# A2.net
KiCad netlist of a schematic drawn in Altium Designer
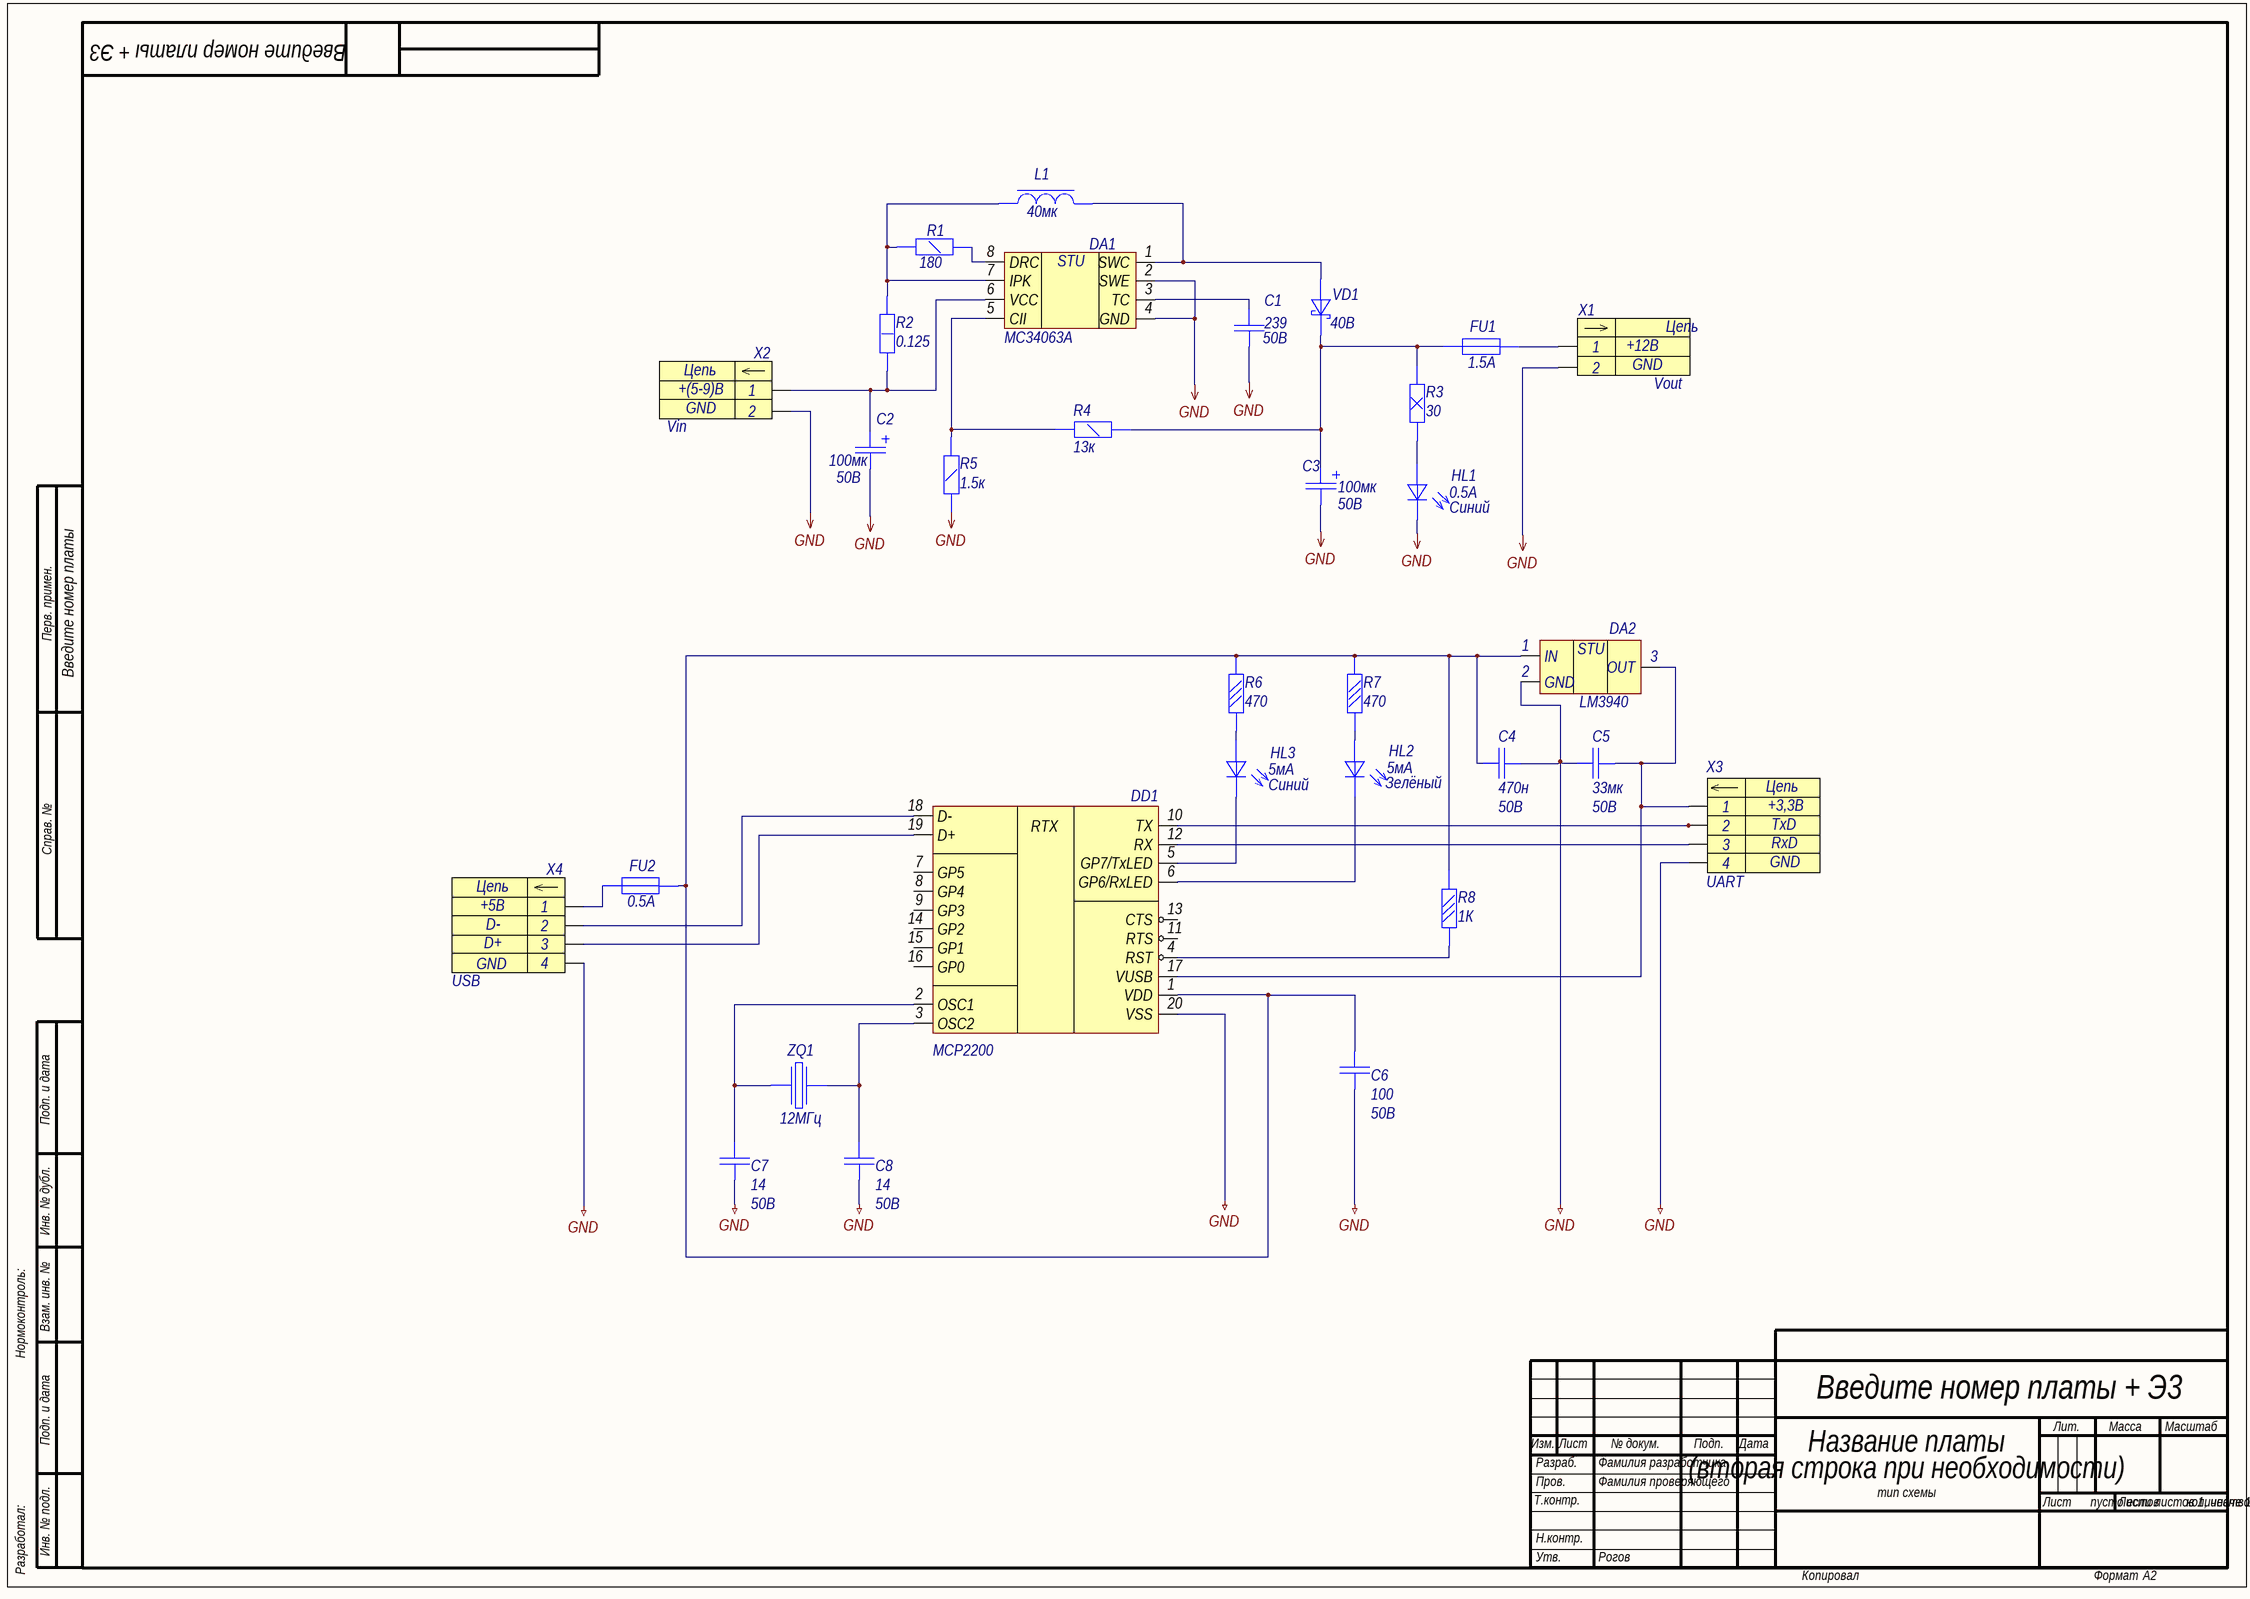
[diagram p0: A2.SchDoc]

(export (version "E")
  (design (tool "Eeschema 10.0.6"))
  (components
    (comp (ref "C1")
      (value "Capacitor")
      (footprint "R0805")
      (fields
        (field (name "ЁМКОСТЬ") "239")
        (field (name "НАПРЯЖЕНИЕ") "50В")
        (field (name "PUBLISHER") "Andrew Danich")
      )
      (libsource (lib "Capacitor GOST") (part "Capacitor"))
    )
    (comp (ref "C2")
      (value "Capacitor-E")
      (footprint "C1206")
      (fields
        (field (name "ЁМКОСТЬ") "100мк")
        (field (name "НАПРЯЖЕНИЕ") "50В")
        (field (name "PUBLISHER") "Олег Литвинов")
      )
      (libsource (lib "Capacitor GOST") (part "Capacitor-E"))
    )
    (comp (ref "C3")
      (value "Capacitor-E")
      (footprint "C1206")
      (fields
        (field (name "ЁМКОСТЬ") "100мк")
        (field (name "НАПРЯЖЕНИЕ") "50В")
        (field (name "PUBLISHER") "Олег Литвинов")
      )
      (libsource (lib "Capacitor GOST") (part "Capacitor-E"))
    )
    (comp (ref "C4")
      (value "470н")
      (footprint "C0805")
      (fields (field (name "VOLTAGE") "50В") (field (name "Comment") "Capacitor"))
      (libsource (lib "Capacitor_GOST") (part "Capacitor"))
    )
    (comp (ref "C5")
      (value "33мк")
      (footprint "C0805")
      (fields (field (name "VOLTAGE") "50В") (field (name "Comment") "Capacitor"))
      (libsource (lib "Capacitor_GOST") (part "Capacitor"))
    )
    (comp (ref "C6")
      (value "100")
      (footprint "C0805")
      (fields (field (name "VOLTAGE") "50В") (field (name "Comment") "Capacitor"))
      (libsource (lib "Capacitor_GOST") (part "Capacitor"))
    )
    (comp (ref "C7")
      (value "14")
      (footprint "C0805")
      (fields (field (name "VOLTAGE") "50В") (field (name "Comment") "Capacitor"))
      (libsource (lib "Capacitor_GOST") (part "Capacitor"))
    )
    (comp (ref "C8")
      (value "14")
      (footprint "C0805")
      (fields (field (name "VOLTAGE") "50В") (field (name "Comment") "Capacitor"))
      (libsource (lib "Capacitor_GOST") (part "Capacitor"))
    )
    (comp (ref "DA1")
      (value "MC34063A")
      (footprint "PCBComponent_1")
      (libsource (lib "MCP2200_UART_USB") (part "MC34063A"))
    )
    (comp (ref "DA2")
      (value "LM3940")
      (footprint "SOT95P255X145-3N")
      (fields (field (name "ITEM ID") "LM3940"))
      (libsource (lib "MCP2200_UART_USB") (part "LM3940"))
    )
    (comp (ref "DD1")
      (value "MCP2200")
      (footprint "SOIC127P1030X265-20N")
      (fields (field (name "WTF") "RTX") (field (name "CREATE") "Litvinov"))
      (libsource (lib "Schlib1") (part "MCP2200"))
    )
    (comp (ref "FU1")
      (value "1.5A")
      (footprint "F1812")
      (fields (field (name "Comment") "Fuse"))
      (libsource (lib "") (part "Fuse_1"))
    )
    (comp (ref "FU2")
      (value "0.5A")
      (footprint "F1812")
      (fields (field (name "Comment") "Fuse"))
      (libsource (lib "Fuse_GOST") (part "Fuse"))
    )
    (comp (ref "HL1")
      (value "LED_3V")
      (footprint "LD0805")
      (fields
        (field (name "ПРЯМОЙ ТОК") "0.5А")
        (field (name "ЦВЕТ") "Синий")
        (field (name "PUBLISHER") "Andrew Danich")
      )
      (libsource (lib "") (part "Led-1_1"))
    )
    (comp (ref "HL2")
      (value "LED_3V")
      (footprint "LD0805")
      (fields
        (field (name "ПРЯМОЙ ТОК") "5мА")
        (field (name "ЦВЕТ") "Зелёный")
        (field (name "PUBLISHER") "Andrew Danich")
      )
      (libsource (lib "Led GOST") (part "Led-1"))
    )
    (comp (ref "HL3")
      (value "LED_3V")
      (footprint "LD0805")
      (fields
        (field (name "ПРЯМОЙ ТОК") "5мА")
        (field (name "ЦВЕТ") "Синий")
        (field (name "PUBLISHER") "Andrew Danich")
      )
      (libsource (lib "Led GOST") (part "Led-1"))
    )
    (comp (ref "L1")
      (value "40мк")
      (footprint "МДГ-2")
      (fields
        (field (name "PART NUMBER") "КИВ18-100")
        (field (name "TOLERANCE") "±10%")
        (field (name "MANUFACTURER") "ОАО \"МСТАТОР\"")
        (field (name "PUBLISHER") "Andrew Danich")
      )
      (libsource (lib "Lib_GOST") (part "Coil"))
    )
    (comp (ref "R1")
      (value "Resistor_0,25W")
      (footprint "R0805")
      (fields (field (name "СОПРОТИВЛЕНИЕ") "180"))
      (libsource (lib "Resistor_GOST") (part "Resistor_0,25W"))
    )
    (comp (ref "R2")
      (value "0.125")
      (footprint "R0805")
      (fields (field (name "Comment") "Resistor_1,0W"))
      (libsource (lib "Resistor_GOST") (part "Resistor_1,0W"))
    )
    (comp (ref "R3")
      (value "Resistor_10,0W")
      (footprint "R0805")
      (fields (field (name "СОПРОТИВЛЕНИЕ") "30"))
      (libsource (lib "Resistor_GOST") (part "Resistor_10,0W"))
    )
    (comp (ref "R4")
      (value "13к")
      (fields (field (name "Comment") "Resistor_0,25W"))
      (libsource (lib "Resistor_GOST") (part "Resistor_0,25W"))
    )
    (comp (ref "R5")
      (value "1.5к")
      (footprint "R0805")
      (fields (field (name "Comment") "Resistor_0,25W"))
      (libsource (lib "Resistor_GOST") (part "Resistor_0,25W"))
    )
    (comp (ref "R6")
      (value "Resistor_0,05W")
      (footprint "R0805")
      (fields (field (name "СОПРОТИВЛЕНИЕ") "470"))
      (libsource (lib "") (part "Resistor_0,05W_2"))
    )
    (comp (ref "R7")
      (value "Resistor_0,05W")
      (footprint "R0805")
      (fields (field (name "СОПРОТИВЛЕНИЕ") "470"))
      (libsource (lib "Resistor_GOST") (part "Resistor_0,05W"))
    )
    (comp (ref "R8")
      (value "1К")
      (footprint "R0805")
      (fields (field (name "Comment") "Resistor_0,05W"))
      (libsource (lib "") (part "Resistor_0,05W_1"))
    )
    (comp (ref "VD1")
      (value "Schottky")
      (footprint "DO-214AC")
      (description "BYV10-40")
      (fields (field (name "МАКСИМАЛЬНОЕ ОБРАТНОЕ НАПРЯЖЕНИЕ") "40В"))
      (libsource (lib "Diode_GOST") (part "Schottky"))
    )
    (comp (ref "X1")
      (value "Vout")
      (footprint "CWF-2")
      (fields (field (name "U") "+12В") (field (name "GND") "GND") (field (name "CREATE") "DeathSpeaker"))
      (libsource (lib "MCP2200_UART_USB") (part "Vout"))
    )
    (comp (ref "X2")
      (value "Vin")
      (footprint "WF-2")
      (fields (field (name "U") "+(5-9)В") (field (name "GND") "GND") (field (name "CREATE") "DeathSpeaker"))
      (libsource (lib "MCP2200_UART_USB") (part "Vin"))
    )
    (comp (ref "X3")
      (value "UART")
      (footprint "UART")
      (fields
        (field (name "GND") "GND")
        (field (name "IN") "TxD")
        (field (name "OUT") "RxD")
        (field (name "U") "+3,3В")
        (field (name "CREATE") "Litvinov")
      )
      (libsource (lib "Schlib1") (part "UART"))
    )
    (comp (ref "X4")
      (value "USB")
      (footprint "USB")
      (fields
        (field (name "U") "+5В")
        (field (name "OUT") "D-")
        (field (name "IN") "D+")
        (field (name "GND") "GND")
        (field (name "CREATE") "Litvinov")
      )
      (libsource (lib "Schlib1") (part "USB"))
    )
    (comp (ref "ZQ1")
      (value "Crystal")
      (footprint "HC-49S")
      (fields (field (name "ЧАСТОТА") "12МГц") (field (name "PUBLISHER") "Andrew Danich"))
      (libsource (lib "Crystal GOST") (part "Crystal"))
    )
  )
  (nets
    (net (code "1") (name "GND") (class "Default")
      (node (ref "C1") (pin "1") (pinfunction "1_1") (pintype "passive"))
      (node (ref "C2") (pin "2") (pinfunction "2_2") (pintype "passive"))
      (node (ref "C3") (pin "2") (pinfunction "2_2") (pintype "passive"))
      (node (ref "C4") (pin "1") (pinfunction "1_1") (pintype "passive"))
      (node (ref "C5") (pin "2") (pinfunction "2_2") (pintype "passive"))
      (node (ref "C6") (pin "2") (pinfunction "2_2") (pintype "passive"))
      (node (ref "C7") (pin "1") (pinfunction "1_1") (pintype "passive"))
      (node (ref "C8") (pin "1") (pinfunction "1_1") (pintype "passive"))
      (node (ref "DA1") (pin "2") (pinfunction "SWE_2") (pintype "passive"))
      (node (ref "DA1") (pin "4") (pinfunction "GND_4") (pintype "passive"))
      (node (ref "DA2") (pin "2") (pinfunction "GND_2") (pintype "passive"))
      (node (ref "DD1") (pin "20") (pinfunction "VSS_20") (pintype "passive"))
      (node (ref "HL1") (pin "2") (pinfunction "К_2") (pintype "passive"))
      (node (ref "R5") (pin "1") (pinfunction "1_1") (pintype "passive"))
      (node (ref "X1") (pin "2") (pinfunction "2_2") (pintype "passive"))
      (node (ref "X2") (pin "2") (pinfunction "2_2") (pintype "passive"))
      (node (ref "X3") (pin "4") (pinfunction "4_4") (pintype "passive"))
      (node (ref "X4") (pin "4") (pinfunction "4_4") (pintype "passive"))
    )
    (net (code "2") (name "Net-(DA1-CII)") (class "Default")
      (node (ref "DA1") (pin "5") (pinfunction "CII_5") (pintype "passive"))
      (node (ref "R4") (pin "1") (pinfunction "1_1") (pintype "passive"))
      (node (ref "R5") (pin "2") (pinfunction "2_2") (pintype "passive"))
    )
    (net (code "3") (name "Net-(DA1-DRC)") (class "Default")
      (node (ref "DA1") (pin "8") (pinfunction "DRC_8") (pintype "passive"))
      (node (ref "R1") (pin "2") (pinfunction "2_2") (pintype "passive"))
    )
    (net (code "4") (name "Net-(DA1-IPK)") (class "Default")
      (node (ref "DA1") (pin "7") (pinfunction "IPK_7") (pintype "passive"))
      (node (ref "L1") (pin "1") (pinfunction "1_1") (pintype "passive"))
      (node (ref "R1") (pin "1") (pinfunction "1_1") (pintype "passive"))
      (node (ref "R2") (pin "2") (pinfunction "2_2") (pintype "passive"))
    )
    (net (code "5") (name "Net-(DA1-SWC)") (class "Default")
      (node (ref "DA1") (pin "1") (pinfunction "SWC_1") (pintype "passive"))
      (node (ref "L1") (pin "2") (pinfunction "2_2") (pintype "passive"))
      (node (ref "VD1") (pin "1") (pinfunction "А_1") (pintype "passive"))
    )
    (net (code "6") (name "Net-(DA1-TC)") (class "Default")
      (node (ref "C1") (pin "2") (pinfunction "2_2") (pintype "passive"))
      (node (ref "DA1") (pin "3") (pinfunction "TC_3") (pintype "passive"))
    )
    (net (code "7") (name "Net-(DA1-VCC)") (class "Default")
      (node (ref "C2") (pin "1") (pinfunction "1_1") (pintype "passive"))
      (node (ref "DA1") (pin "6") (pinfunction "VCC_6") (pintype "passive"))
      (node (ref "R2") (pin "1") (pinfunction "1_1") (pintype "passive"))
      (node (ref "X2") (pin "1") (pinfunction "1_1") (pintype "passive"))
    )
    (net (code "8") (name "Net-(DA2-IN)") (class "Default")
      (node (ref "C4") (pin "2") (pinfunction "2_2") (pintype "passive"))
      (node (ref "C6") (pin "1") (pinfunction "1_1") (pintype "passive"))
      (node (ref "DA2") (pin "1") (pinfunction "IN_1") (pintype "passive"))
      (node (ref "DD1") (pin "1") (pinfunction "VDD_1") (pintype "passive"))
      (node (ref "FU2") (pin "1") (pinfunction "1_1") (pintype "passive"))
      (node (ref "R6") (pin "2") (pinfunction "2_2") (pintype "passive"))
      (node (ref "R7") (pin "2") (pinfunction "2_2") (pintype "passive"))
      (node (ref "R8") (pin "2") (pinfunction "2_2") (pintype "passive"))
    )
    (net (code "9") (name "Net-(DA2-OUT)") (class "Default")
      (node (ref "C5") (pin "1") (pinfunction "1_1") (pintype "passive"))
      (node (ref "DA2") (pin "3") (pinfunction "OUT_3") (pintype "passive"))
      (node (ref "DD1") (pin "17") (pinfunction "VUSB_17") (pintype "passive"))
      (node (ref "X3") (pin "1") (pinfunction "1_1") (pintype "passive"))
    )
    (net (code "10") (name "Net-(DD1-D+)") (class "Default")
      (node (ref "DD1") (pin "19") (pinfunction "D+_19") (pintype "passive"))
      (node (ref "X4") (pin "3") (pinfunction "3_3") (pintype "passive"))
    )
    (net (code "11") (name "Net-(DD1-D-)") (class "Default")
      (node (ref "DD1") (pin "18") (pinfunction "D-_18") (pintype "passive"))
      (node (ref "X4") (pin "2") (pinfunction "2_2") (pintype "passive"))
    )
    (net (code "12") (name "Net-(DD1-GP6{slash}RxLED)") (class "Default")
      (node (ref "DD1") (pin "6") (pinfunction "GP6/RxLED_6") (pintype "passive"))
      (node (ref "HL2") (pin "2") (pinfunction "К_2") (pintype "passive"))
    )
    (net (code "13") (name "Net-(DD1-GP7{slash}TxLED)") (class "Default")
      (node (ref "DD1") (pin "5") (pinfunction "GP7/TxLED_5") (pintype "passive"))
      (node (ref "HL3") (pin "2") (pinfunction "К_2") (pintype "passive"))
    )
    (net (code "14") (name "Net-(DD1-OSC1)") (class "Default")
      (node (ref "C7") (pin "2") (pinfunction "2_2") (pintype "passive"))
      (node (ref "DD1") (pin "2") (pinfunction "OSC1_2") (pintype "passive"))
      (node (ref "ZQ1") (pin "1") (pinfunction "1_1") (pintype "passive"))
    )
    (net (code "15") (name "Net-(DD1-OSC2)") (class "Default")
      (node (ref "C8") (pin "2") (pinfunction "2_2") (pintype "passive"))
      (node (ref "DD1") (pin "3") (pinfunction "OSC2_3") (pintype "passive"))
      (node (ref "ZQ1") (pin "3") (pinfunction "3_3") (pintype "passive"))
    )
    (net (code "16") (name "Net-(DD1-RST)") (class "Default")
      (node (ref "DD1") (pin "4") (pinfunction "RST_4") (pintype "passive"))
      (node (ref "R8") (pin "1") (pinfunction "1_1") (pintype "passive"))
    )
    (net (code "17") (name "Net-(DD1-RX)") (class "Default")
      (node (ref "DD1") (pin "12") (pinfunction "RX_12") (pintype "passive"))
      (node (ref "X3") (pin "3") (pinfunction "3_3") (pintype "passive"))
    )
    (net (code "18") (name "Net-(DD1-TX)") (class "Default")
      (node (ref "DD1") (pin "10") (pinfunction "TX_10") (pintype "passive"))
      (node (ref "X3") (pin "2") (pinfunction "2_2") (pintype "passive"))
    )
    (net (code "19") (name "Net-(FU1-Pad1)") (class "Default")
      (node (ref "FU1") (pin "1") (pinfunction "1_1") (pintype "passive"))
      (node (ref "X1") (pin "1") (pinfunction "1_1") (pintype "passive"))
    )
    (net (code "20") (name "Net-(FU2-Pad2)") (class "Default")
      (node (ref "FU2") (pin "2") (pinfunction "2_2") (pintype "passive"))
      (node (ref "X4") (pin "1") (pinfunction "1_1") (pintype "passive"))
    )
    (net (code "21") (name "Net-(HL1-А)") (class "Default")
      (node (ref "HL1") (pin "1") (pinfunction "А_1") (pintype "passive"))
      (node (ref "R3") (pin "1") (pinfunction "1_1") (pintype "passive"))
    )
    (net (code "22") (name "Net-(HL2-А)") (class "Default")
      (node (ref "HL2") (pin "1") (pinfunction "А_1") (pintype "passive"))
      (node (ref "R7") (pin "1") (pinfunction "1_1") (pintype "passive"))
    )
    (net (code "23") (name "Net-(HL3-А)") (class "Default")
      (node (ref "HL3") (pin "1") (pinfunction "А_1") (pintype "passive"))
      (node (ref "R6") (pin "1") (pinfunction "1_1") (pintype "passive"))
    )
    (net (code "24") (name "Net-(VD1-К)") (class "Default")
      (node (ref "C3") (pin "1") (pinfunction "1_1") (pintype "passive"))
      (node (ref "FU1") (pin "2") (pinfunction "2_2") (pintype "passive"))
      (node (ref "R3") (pin "2") (pinfunction "2_2") (pintype "passive"))
      (node (ref "R4") (pin "2") (pinfunction "2_2") (pintype "passive"))
      (node (ref "VD1") (pin "2") (pinfunction "К_2") (pintype "passive"))
    )
    (net (code "25") (name "unconnected-(DD1-CTS-Pad13)") (class "Default")
      (node (ref "DD1") (pin "13") (pinfunction "CTS_13") (pintype "passive"))
    )
    (net (code "26") (name "unconnected-(DD1-GP0-Pad16)") (class "Default")
      (node (ref "DD1") (pin "16") (pinfunction "GP0_16") (pintype "passive"))
    )
    (net (code "27") (name "unconnected-(DD1-GP1-Pad15)") (class "Default")
      (node (ref "DD1") (pin "15") (pinfunction "GP1_15") (pintype "passive"))
    )
    (net (code "28") (name "unconnected-(DD1-GP2-Pad14)") (class "Default")
      (node (ref "DD1") (pin "14") (pinfunction "GP2_14") (pintype "passive"))
    )
    (net (code "29") (name "unconnected-(DD1-GP3-Pad9)") (class "Default")
      (node (ref "DD1") (pin "9") (pinfunction "GP3_9") (pintype "passive"))
    )
    (net (code "30") (name "unconnected-(DD1-GP4-Pad8)") (class "Default")
      (node (ref "DD1") (pin "8") (pinfunction "GP4_8") (pintype "passive"))
    )
    (net (code "31") (name "unconnected-(DD1-GP5-Pad7)") (class "Default")
      (node (ref "DD1") (pin "7") (pinfunction "GP5_7") (pintype "passive"))
    )
    (net (code "32") (name "unconnected-(DD1-RTS-Pad11)") (class "Default")
      (node (ref "DD1") (pin "11") (pinfunction "RTS_11") (pintype "passive"))
    )
  )
)
